# power-linear-LP38692.net
KiCad netlist of a schematic drawn in EAGLE
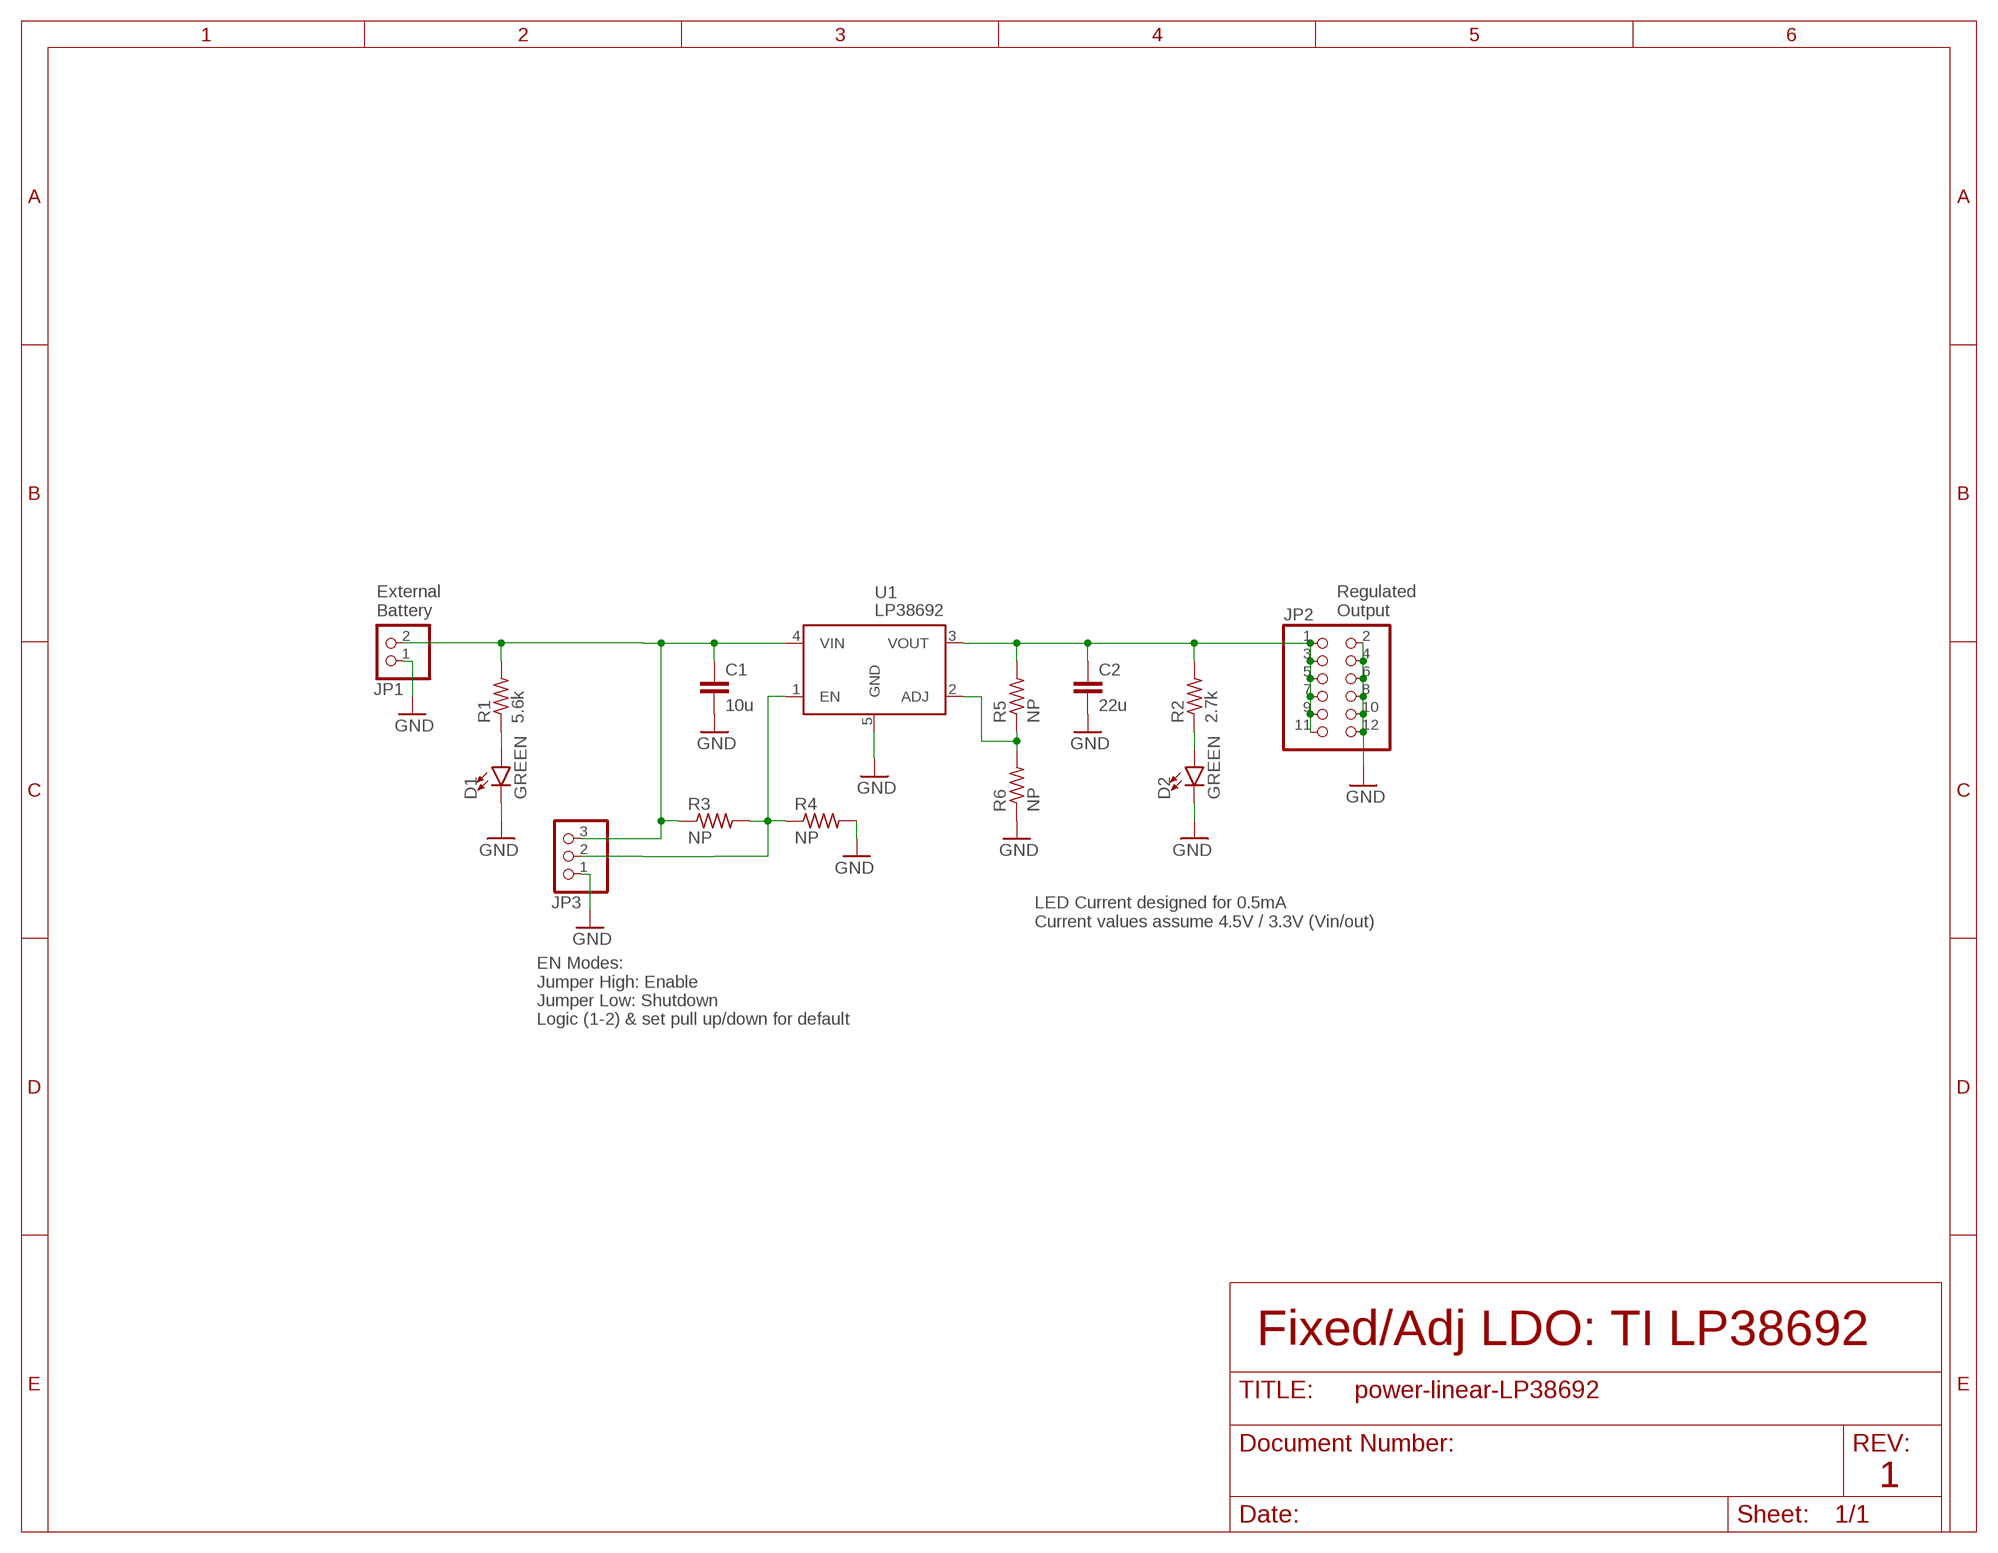
[diagram p0: schematic, sheet 1]

(export (version "E")
  (design (tool "Eeschema 10.0.6"))
  (components
    (comp (ref "C1")
      (value "10u")
      (footprint "eagle-import:.0805-B-NOSILK")
      (libsource (lib "eagle-import") (part "C-EU0805-B-NOSILK"))
    )
    (comp (ref "C2")
      (value "22u")
      (footprint "eagle-import:1206-B")
      (libsource (lib "eagle-import") (part "C-EU1206-B"))
    )
    (comp (ref "D1")
      (value "GREEN")
      (footprint "eagle-import:LED-0603")
      (libsource (lib "eagle-import") (part "LED-GREEN0603"))
    )
    (comp (ref "D2")
      (value "GREEN")
      (footprint "eagle-import:LED-0603")
      (libsource (lib "eagle-import") (part "LED-GREEN0603"))
    )
    (comp (ref "JP1")
      (value "PINHD-1X2")
      (footprint "eagle-import:1X02")
      (libsource (lib "eagle-import") (part "PINHD-1X2"))
    )
    (comp (ref "JP2")
      (value "PINHD-2X6")
      (footprint "eagle-import:2X06")
      (libsource (lib "eagle-import") (part "PINHD-2X6"))
    )
    (comp (ref "JP3")
      (value "PINHD-1X3")
      (footprint "eagle-import:1X03")
      (libsource (lib "eagle-import") (part "PINHD-1X3"))
    )
    (comp (ref "R1")
      (value "5.6k")
      (footprint "eagle-import:.0603-B-NOSILK")
      (libsource (lib "eagle-import") (part "R-US_0603-B-NOSILK"))
    )
    (comp (ref "R2")
      (value "2.7k")
      (footprint "eagle-import:.0603-B-NOSILK")
      (libsource (lib "eagle-import") (part "R-US_0603-B-NOSILK"))
    )
    (comp (ref "R3")
      (value "NP")
      (footprint "eagle-import:.0402-B-NOSILK")
      (libsource (lib "eagle-import") (part "R-US_0402-B-NOSILK"))
    )
    (comp (ref "R4")
      (value "NP")
      (footprint "eagle-import:.0402-B-NOSILK")
      (libsource (lib "eagle-import") (part "R-US_0402-B-NOSILK"))
    )
    (comp (ref "R5")
      (value "NP")
      (footprint "eagle-import:.0402-B-NOSILK")
      (libsource (lib "eagle-import") (part "R-US_0402-B-NOSILK"))
    )
    (comp (ref "R6")
      (value "NP")
      (footprint "eagle-import:.0402-B-NOSILK")
      (libsource (lib "eagle-import") (part "R-US_0402-B-NOSILK"))
    )
    (comp (ref "U1")
      (value "LP38692")
      (footprint "eagle-import:SOT223-5")
      (libsource (lib "eagle-import") (part "LP38692"))
    )
  )
  (nets
    (net (code "1") (name "GND") (class "Default")
      (node (ref "C1") (pin "2") (pinfunction "2_2") (pintype "passive"))
      (node (ref "C2") (pin "2") (pinfunction "2_2") (pintype "passive"))
      (node (ref "D1") (pin "C") (pinfunction "C_C") (pintype "passive"))
      (node (ref "D2") (pin "C") (pinfunction "C_C") (pintype "passive"))
      (node (ref "JP1") (pin "1") (pinfunction "1_1") (pintype "passive"))
      (node (ref "JP2") (pin "10") (pinfunction "10_10") (pintype "passive"))
      (node (ref "JP2") (pin "12") (pinfunction "12_12") (pintype "passive"))
      (node (ref "JP2") (pin "2") (pinfunction "2_2") (pintype "passive"))
      (node (ref "JP2") (pin "4") (pinfunction "4_4") (pintype "passive"))
      (node (ref "JP2") (pin "6") (pinfunction "6_6") (pintype "passive"))
      (node (ref "JP2") (pin "8") (pinfunction "8_8") (pintype "passive"))
      (node (ref "JP3") (pin "1") (pinfunction "1_1") (pintype "passive"))
      (node (ref "R4") (pin "2") (pinfunction "2_2") (pintype "passive"))
      (node (ref "R6") (pin "1") (pinfunction "1_1") (pintype "passive"))
      (node (ref "U1") (pin "5") (pinfunction "GND_5") (pintype "power_in"))
    )
    (net (code "2") (name "Net-(D1-PadA)") (class "Default")
      (node (ref "D1") (pin "A") (pinfunction "A_A") (pintype "passive"))
      (node (ref "R1") (pin "1") (pinfunction "1_1") (pintype "passive"))
    )
    (net (code "3") (name "Net-(D2-PadA)") (class "Default")
      (node (ref "D2") (pin "A") (pinfunction "A_A") (pintype "passive"))
      (node (ref "R2") (pin "1") (pinfunction "1_1") (pintype "passive"))
    )
    (net (code "4") (name "Net-(U1-ADJ)") (class "Default")
      (node (ref "R5") (pin "1") (pinfunction "1_1") (pintype "passive"))
      (node (ref "R6") (pin "2") (pinfunction "2_2") (pintype "passive"))
      (node (ref "U1") (pin "2") (pinfunction "ADJ_2") (pintype "input"))
    )
    (net (code "5") (name "Net-(U1-EN)") (class "Default")
      (node (ref "JP3") (pin "2") (pinfunction "2_2") (pintype "passive"))
      (node (ref "R3") (pin "2") (pinfunction "2_2") (pintype "passive"))
      (node (ref "R4") (pin "1") (pinfunction "1_1") (pintype "passive"))
      (node (ref "U1") (pin "1") (pinfunction "EN_1") (pintype "input"))
    )
    (net (code "6") (name "Net-(U1-VIN)") (class "Default")
      (node (ref "C1") (pin "1") (pinfunction "1_1") (pintype "passive"))
      (node (ref "JP1") (pin "2") (pinfunction "2_2") (pintype "passive"))
      (node (ref "JP3") (pin "3") (pinfunction "3_3") (pintype "passive"))
      (node (ref "R1") (pin "2") (pinfunction "2_2") (pintype "passive"))
      (node (ref "R3") (pin "1") (pinfunction "1_1") (pintype "passive"))
      (node (ref "U1") (pin "4") (pinfunction "VIN_4") (pintype "power_in"))
    )
    (net (code "7") (name "Net-(U1-VOUT)") (class "Default")
      (node (ref "C2") (pin "1") (pinfunction "1_1") (pintype "passive"))
      (node (ref "JP2") (pin "1") (pinfunction "1_1") (pintype "passive"))
      (node (ref "JP2") (pin "11") (pinfunction "11_11") (pintype "passive"))
      (node (ref "JP2") (pin "3") (pinfunction "3_3") (pintype "passive"))
      (node (ref "JP2") (pin "5") (pinfunction "5_5") (pintype "passive"))
      (node (ref "JP2") (pin "7") (pinfunction "7_7") (pintype "passive"))
      (node (ref "JP2") (pin "9") (pinfunction "9_9") (pintype "passive"))
      (node (ref "R2") (pin "2") (pinfunction "2_2") (pintype "passive"))
      (node (ref "R5") (pin "2") (pinfunction "2_2") (pintype "passive"))
      (node (ref "U1") (pin "3") (pinfunction "VOUT_3") (pintype "power_in"))
    )
  )
)
